# Zavrsni_Rad.net
KiCad netlist of a schematic drawn in EAGLE
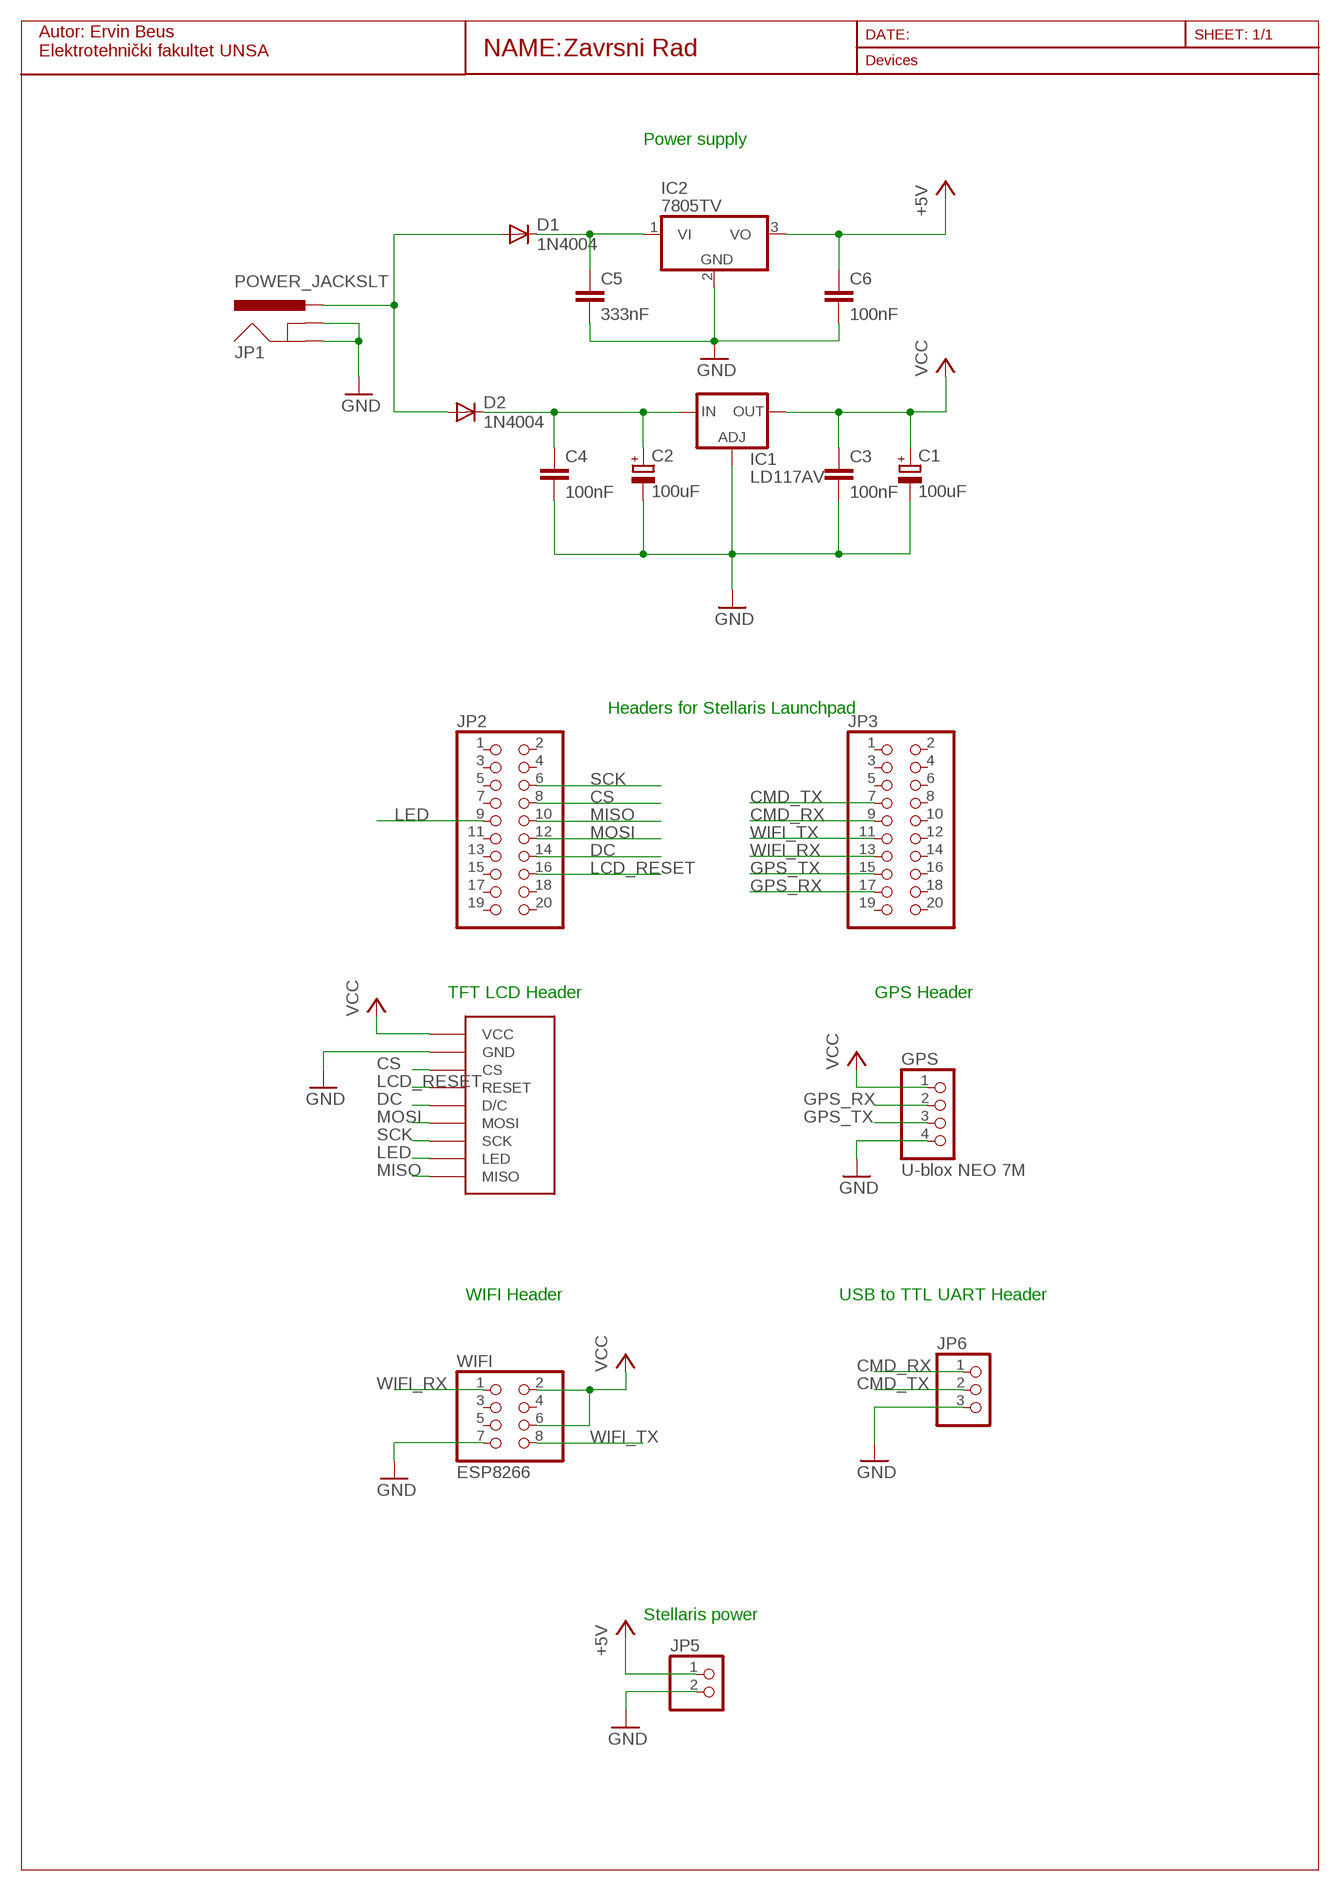
[diagram p0: schematic, sheet 1]

(export (version "E")
  (design (tool "Eeschema 10.0.6"))
  (components
    (comp (ref "C1")
      (value "100uF")
      (footprint "eagle-import:E2,5-6E")
      (libsource (lib "eagle-import") (part "CPOL-EUE2,5-6E"))
    )
    (comp (ref "C2")
      (value "100uF")
      (footprint "eagle-import:E2,5-6E")
      (libsource (lib "eagle-import") (part "CPOL-EUE2,5-6E"))
    )
    (comp (ref "C3")
      (value "100nF")
      (footprint "eagle-import:C025-024X044")
      (libsource (lib "eagle-import") (part "C-EU025-024X044"))
    )
    (comp (ref "C4")
      (value "100nF")
      (footprint "eagle-import:C025-024X044")
      (libsource (lib "eagle-import") (part "C-EU025-024X044"))
    )
    (comp (ref "C5")
      (value "333nF")
      (footprint "eagle-import:C025-024X044")
      (libsource (lib "eagle-import") (part "C-EU025-024X044"))
    )
    (comp (ref "C6")
      (value "100nF")
      (footprint "eagle-import:C025-024X044")
      (libsource (lib "eagle-import") (part "C-EU025-024X044"))
    )
    (comp (ref "D1")
      (value "1N4004")
      (footprint "eagle-import:DO41-10")
      (libsource (lib "eagle-import") (part "1N4004"))
    )
    (comp (ref "D2")
      (value "1N4004")
      (footprint "eagle-import:DO41-10")
      (libsource (lib "eagle-import") (part "1N4004"))
    )
    (comp (ref "GPS")
      (value "U-blox NEO 7M")
      (footprint "eagle-import:1X04")
      (libsource (lib "eagle-import") (part "PINHD-1X4"))
    )
    (comp (ref "IC1")
      (value "LD117AV")
      (footprint "eagle-import:TO220L1")
      (libsource (lib "eagle-import") (part "LD117A?V"))
    )
    (comp (ref "IC2")
      (value "7805TV")
      (footprint "eagle-import:TO220V")
      (libsource (lib "eagle-import") (part "78TV05"))
    )
    (comp (ref "JP1")
      (value "POWER_JACKSLT")
      (footprint "eagle-import:POWER_JACK_SLOT")
      (libsource (lib "eagle-import") (part "POWER_JACKSLT"))
    )
    (comp (ref "JP2")
      (value "PINHD-2X10")
      (footprint "eagle-import:2X10")
      (libsource (lib "eagle-import") (part "PINHD-2X10"))
    )
    (comp (ref "JP3")
      (value "PINHD-2X10")
      (footprint "eagle-import:2X10")
      (libsource (lib "eagle-import") (part "PINHD-2X10"))
    )
    (comp (ref "JP5")
      (value "PINHD-1X2")
      (footprint "eagle-import:1X02")
      (libsource (lib "eagle-import") (part "PINHD-1X2"))
    )
    (comp (ref "JP6")
      (value "PINHD-1X3")
      (footprint "eagle-import:1X03")
      (libsource (lib "eagle-import") (part "PINHD-1X3"))
    )
    (comp (ref "TFTLCD")
      (value "SPI_TFT_DISPLAY")
      (footprint "eagle-import:SPI_DISPLAY")
      (libsource (lib "eagle-import") (part "SPI_TFT_DISPLAY"))
    )
    (comp (ref "WIFI")
      (value "ESP8266")
      (footprint "eagle-import:2X04")
      (libsource (lib "eagle-import") (part "PINHD-2X4"))
    )
  )
  (nets
    (net (code "1") (name "+5V") (class "Default")
      (node (ref "C6") (pin "1") (pinfunction "1_1") (pintype "passive"))
      (node (ref "IC2") (pin "3") (pinfunction "VO_3") (pintype "passive"))
      (node (ref "JP5") (pin "1") (pinfunction "1_1") (pintype "passive"))
    )
    (net (code "2") (name "/CMD_RX") (class "Default")
      (node (ref "JP3") (pin "9") (pinfunction "9_9") (pintype "passive"))
      (node (ref "JP6") (pin "1") (pinfunction "1_1") (pintype "passive"))
    )
    (net (code "3") (name "/CMD_TX") (class "Default")
      (node (ref "JP3") (pin "7") (pinfunction "7_7") (pintype "passive"))
      (node (ref "JP6") (pin "2") (pinfunction "2_2") (pintype "passive"))
    )
    (net (code "4") (name "/CS") (class "Default")
      (node (ref "JP2") (pin "8") (pinfunction "8_8") (pintype "passive"))
      (node (ref "TFTLCD") (pin "CS") (pinfunction "CS_CS") (pintype "bidirectional"))
    )
    (net (code "5") (name "/DC") (class "Default")
      (node (ref "JP2") (pin "14") (pinfunction "14_14") (pintype "passive"))
      (node (ref "TFTLCD") (pin "D/C") (pinfunction "D/C_D/C") (pintype "bidirectional"))
    )
    (net (code "6") (name "/GPS_RX") (class "Default")
      (node (ref "GPS") (pin "2") (pinfunction "2_2") (pintype "passive"))
      (node (ref "JP3") (pin "17") (pinfunction "17_17") (pintype "passive"))
    )
    (net (code "7") (name "/GPS_TX") (class "Default")
      (node (ref "GPS") (pin "3") (pinfunction "3_3") (pintype "passive"))
      (node (ref "JP3") (pin "15") (pinfunction "15_15") (pintype "passive"))
    )
    (net (code "8") (name "/LCD_RESET") (class "Default")
      (node (ref "JP2") (pin "16") (pinfunction "16_16") (pintype "passive"))
      (node (ref "TFTLCD") (pin "RESET") (pinfunction "RESET_RESET") (pintype "bidirectional"))
    )
    (net (code "9") (name "/LED") (class "Default")
      (node (ref "JP2") (pin "9") (pinfunction "9_9") (pintype "passive"))
      (node (ref "TFTLCD") (pin "LED") (pinfunction "LED_LED") (pintype "bidirectional"))
    )
    (net (code "10") (name "/MISO") (class "Default")
      (node (ref "JP2") (pin "10") (pinfunction "10_10") (pintype "passive"))
      (node (ref "TFTLCD") (pin "MISO") (pinfunction "MISO_MISO") (pintype "bidirectional"))
    )
    (net (code "11") (name "/MOSI") (class "Default")
      (node (ref "JP2") (pin "12") (pinfunction "12_12") (pintype "passive"))
      (node (ref "TFTLCD") (pin "MOSI") (pinfunction "MOSI_MOSI") (pintype "bidirectional"))
    )
    (net (code "12") (name "/SCK") (class "Default")
      (node (ref "JP2") (pin "6") (pinfunction "6_6") (pintype "passive"))
      (node (ref "TFTLCD") (pin "SCK") (pinfunction "SCK_SCK") (pintype "bidirectional"))
    )
    (net (code "13") (name "/WIFI_RX") (class "Default")
      (node (ref "JP3") (pin "13") (pinfunction "13_13") (pintype "passive"))
      (node (ref "WIFI") (pin "1") (pinfunction "1_1") (pintype "passive"))
    )
    (net (code "14") (name "/WIFI_TX") (class "Default")
      (node (ref "JP3") (pin "11") (pinfunction "11_11") (pintype "passive"))
      (node (ref "WIFI") (pin "8") (pinfunction "8_8") (pintype "passive"))
    )
    (net (code "15") (name "GND") (class "Default")
      (node (ref "C1") (pin "-") (pinfunction "-_-") (pintype "passive"))
      (node (ref "C2") (pin "-") (pinfunction "-_-") (pintype "passive"))
      (node (ref "C3") (pin "2") (pinfunction "2_2") (pintype "passive"))
      (node (ref "C4") (pin "2") (pinfunction "2_2") (pintype "passive"))
      (node (ref "C5") (pin "2") (pinfunction "2_2") (pintype "passive"))
      (node (ref "C6") (pin "2") (pinfunction "2_2") (pintype "passive"))
      (node (ref "GPS") (pin "4") (pinfunction "4_4") (pintype "passive"))
      (node (ref "IC1") (pin "1") (pinfunction "ADJ_1") (pintype "input"))
      (node (ref "IC2") (pin "2") (pinfunction "GND_2") (pintype "passive"))
      (node (ref "JP1") (pin "GND@1") (pinfunction "GNDBREAK_GND@1") (pintype "power_in"))
      (node (ref "JP1") (pin "GND@2") (pinfunction "GND_GND@2") (pintype "power_in"))
      (node (ref "JP5") (pin "2") (pinfunction "2_2") (pintype "passive"))
      (node (ref "JP6") (pin "3") (pinfunction "3_3") (pintype "passive"))
      (node (ref "TFTLCD") (pin "GND") (pinfunction "GND_GND") (pintype "power_in"))
      (node (ref "WIFI") (pin "7") (pinfunction "7_7") (pintype "passive"))
    )
    (net (code "16") (name "Net-(D1-PadA)") (class "Default")
      (node (ref "D1") (pin "A") (pinfunction "A_A") (pintype "passive"))
      (node (ref "D2") (pin "A") (pinfunction "A_A") (pintype "passive"))
      (node (ref "JP1") (pin "PWR") (pinfunction "PWR_PWR") (pintype "power_in"))
    )
    (net (code "17") (name "Net-(IC1-IN)") (class "Default")
      (node (ref "C2") (pin "+") (pinfunction "+_+") (pintype "passive"))
      (node (ref "C4") (pin "1") (pinfunction "1_1") (pintype "passive"))
      (node (ref "D2") (pin "C") (pinfunction "C_C") (pintype "passive"))
      (node (ref "IC1") (pin "3") (pinfunction "IN_3") (pintype "input"))
    )
    (net (code "18") (name "Net-(IC2-VI)") (class "Default")
      (node (ref "C5") (pin "1") (pinfunction "1_1") (pintype "passive"))
      (node (ref "D1") (pin "C") (pinfunction "C_C") (pintype "passive"))
      (node (ref "IC2") (pin "1") (pinfunction "VI_1") (pintype "input"))
    )
    (net (code "19") (name "VCC") (class "Default")
      (node (ref "C1") (pin "+") (pinfunction "+_+") (pintype "passive"))
      (node (ref "C3") (pin "1") (pinfunction "1_1") (pintype "passive"))
      (node (ref "GPS") (pin "1") (pinfunction "1_1") (pintype "passive"))
      (node (ref "IC1") (pin "2") (pinfunction "OUT_2") (pintype "passive"))
      (node (ref "TFTLCD") (pin "VCC") (pinfunction "VCC_VCC") (pintype "power_in"))
      (node (ref "WIFI") (pin "2") (pinfunction "2_2") (pintype "passive"))
      (node (ref "WIFI") (pin "6") (pinfunction "6_6") (pintype "passive"))
    )
    (net (code "20") (name "unconnected-(JP2-Pad1)") (class "Default")
      (node (ref "JP2") (pin "1") (pinfunction "1_1") (pintype "passive"))
    )
    (net (code "21") (name "unconnected-(JP2-Pad2)") (class "Default")
      (node (ref "JP2") (pin "2") (pinfunction "2_2") (pintype "passive"))
    )
    (net (code "22") (name "unconnected-(JP2-Pad3)") (class "Default")
      (node (ref "JP2") (pin "3") (pinfunction "3_3") (pintype "passive"))
    )
    (net (code "23") (name "unconnected-(JP2-Pad4)") (class "Default")
      (node (ref "JP2") (pin "4") (pinfunction "4_4") (pintype "passive"))
    )
    (net (code "24") (name "unconnected-(JP2-Pad5)") (class "Default")
      (node (ref "JP2") (pin "5") (pinfunction "5_5") (pintype "passive"))
    )
    (net (code "25") (name "unconnected-(JP2-Pad7)") (class "Default")
      (node (ref "JP2") (pin "7") (pinfunction "7_7") (pintype "passive"))
    )
    (net (code "26") (name "unconnected-(JP2-Pad11)") (class "Default")
      (node (ref "JP2") (pin "11") (pinfunction "11_11") (pintype "passive"))
    )
    (net (code "27") (name "unconnected-(JP2-Pad13)") (class "Default")
      (node (ref "JP2") (pin "13") (pinfunction "13_13") (pintype "passive"))
    )
    (net (code "28") (name "unconnected-(JP2-Pad15)") (class "Default")
      (node (ref "JP2") (pin "15") (pinfunction "15_15") (pintype "passive"))
    )
    (net (code "29") (name "unconnected-(JP2-Pad17)") (class "Default")
      (node (ref "JP2") (pin "17") (pinfunction "17_17") (pintype "passive"))
    )
    (net (code "30") (name "unconnected-(JP2-Pad18)") (class "Default")
      (node (ref "JP2") (pin "18") (pinfunction "18_18") (pintype "passive"))
    )
    (net (code "31") (name "unconnected-(JP2-Pad19)") (class "Default")
      (node (ref "JP2") (pin "19") (pinfunction "19_19") (pintype "passive"))
    )
    (net (code "32") (name "unconnected-(JP2-Pad20)") (class "Default")
      (node (ref "JP2") (pin "20") (pinfunction "20_20") (pintype "passive"))
    )
    (net (code "33") (name "unconnected-(JP3-Pad1)") (class "Default")
      (node (ref "JP3") (pin "1") (pinfunction "1_1") (pintype "passive"))
    )
    (net (code "34") (name "unconnected-(JP3-Pad2)") (class "Default")
      (node (ref "JP3") (pin "2") (pinfunction "2_2") (pintype "passive"))
    )
    (net (code "35") (name "unconnected-(JP3-Pad3)") (class "Default")
      (node (ref "JP3") (pin "3") (pinfunction "3_3") (pintype "passive"))
    )
    (net (code "36") (name "unconnected-(JP3-Pad4)") (class "Default")
      (node (ref "JP3") (pin "4") (pinfunction "4_4") (pintype "passive"))
    )
    (net (code "37") (name "unconnected-(JP3-Pad5)") (class "Default")
      (node (ref "JP3") (pin "5") (pinfunction "5_5") (pintype "passive"))
    )
    (net (code "38") (name "unconnected-(JP3-Pad6)") (class "Default")
      (node (ref "JP3") (pin "6") (pinfunction "6_6") (pintype "passive"))
    )
    (net (code "39") (name "unconnected-(JP3-Pad8)") (class "Default")
      (node (ref "JP3") (pin "8") (pinfunction "8_8") (pintype "passive"))
    )
    (net (code "40") (name "unconnected-(JP3-Pad10)") (class "Default")
      (node (ref "JP3") (pin "10") (pinfunction "10_10") (pintype "passive"))
    )
    (net (code "41") (name "unconnected-(JP3-Pad12)") (class "Default")
      (node (ref "JP3") (pin "12") (pinfunction "12_12") (pintype "passive"))
    )
    (net (code "42") (name "unconnected-(JP3-Pad14)") (class "Default")
      (node (ref "JP3") (pin "14") (pinfunction "14_14") (pintype "passive"))
    )
    (net (code "43") (name "unconnected-(JP3-Pad16)") (class "Default")
      (node (ref "JP3") (pin "16") (pinfunction "16_16") (pintype "passive"))
    )
    (net (code "44") (name "unconnected-(JP3-Pad18)") (class "Default")
      (node (ref "JP3") (pin "18") (pinfunction "18_18") (pintype "passive"))
    )
    (net (code "45") (name "unconnected-(JP3-Pad19)") (class "Default")
      (node (ref "JP3") (pin "19") (pinfunction "19_19") (pintype "passive"))
    )
    (net (code "46") (name "unconnected-(JP3-Pad20)") (class "Default")
      (node (ref "JP3") (pin "20") (pinfunction "20_20") (pintype "passive"))
    )
    (net (code "47") (name "unconnected-(WIFI-Pad3)") (class "Default")
      (node (ref "WIFI") (pin "3") (pinfunction "3_3") (pintype "passive"))
    )
    (net (code "48") (name "unconnected-(WIFI-Pad4)") (class "Default")
      (node (ref "WIFI") (pin "4") (pinfunction "4_4") (pintype "passive"))
    )
    (net (code "49") (name "unconnected-(WIFI-Pad5)") (class "Default")
      (node (ref "WIFI") (pin "5") (pinfunction "5_5") (pintype "passive"))
    )
  )
)
